# EasyEDApro.net
KiCad netlist of a schematic drawn in EasyEDA Pro
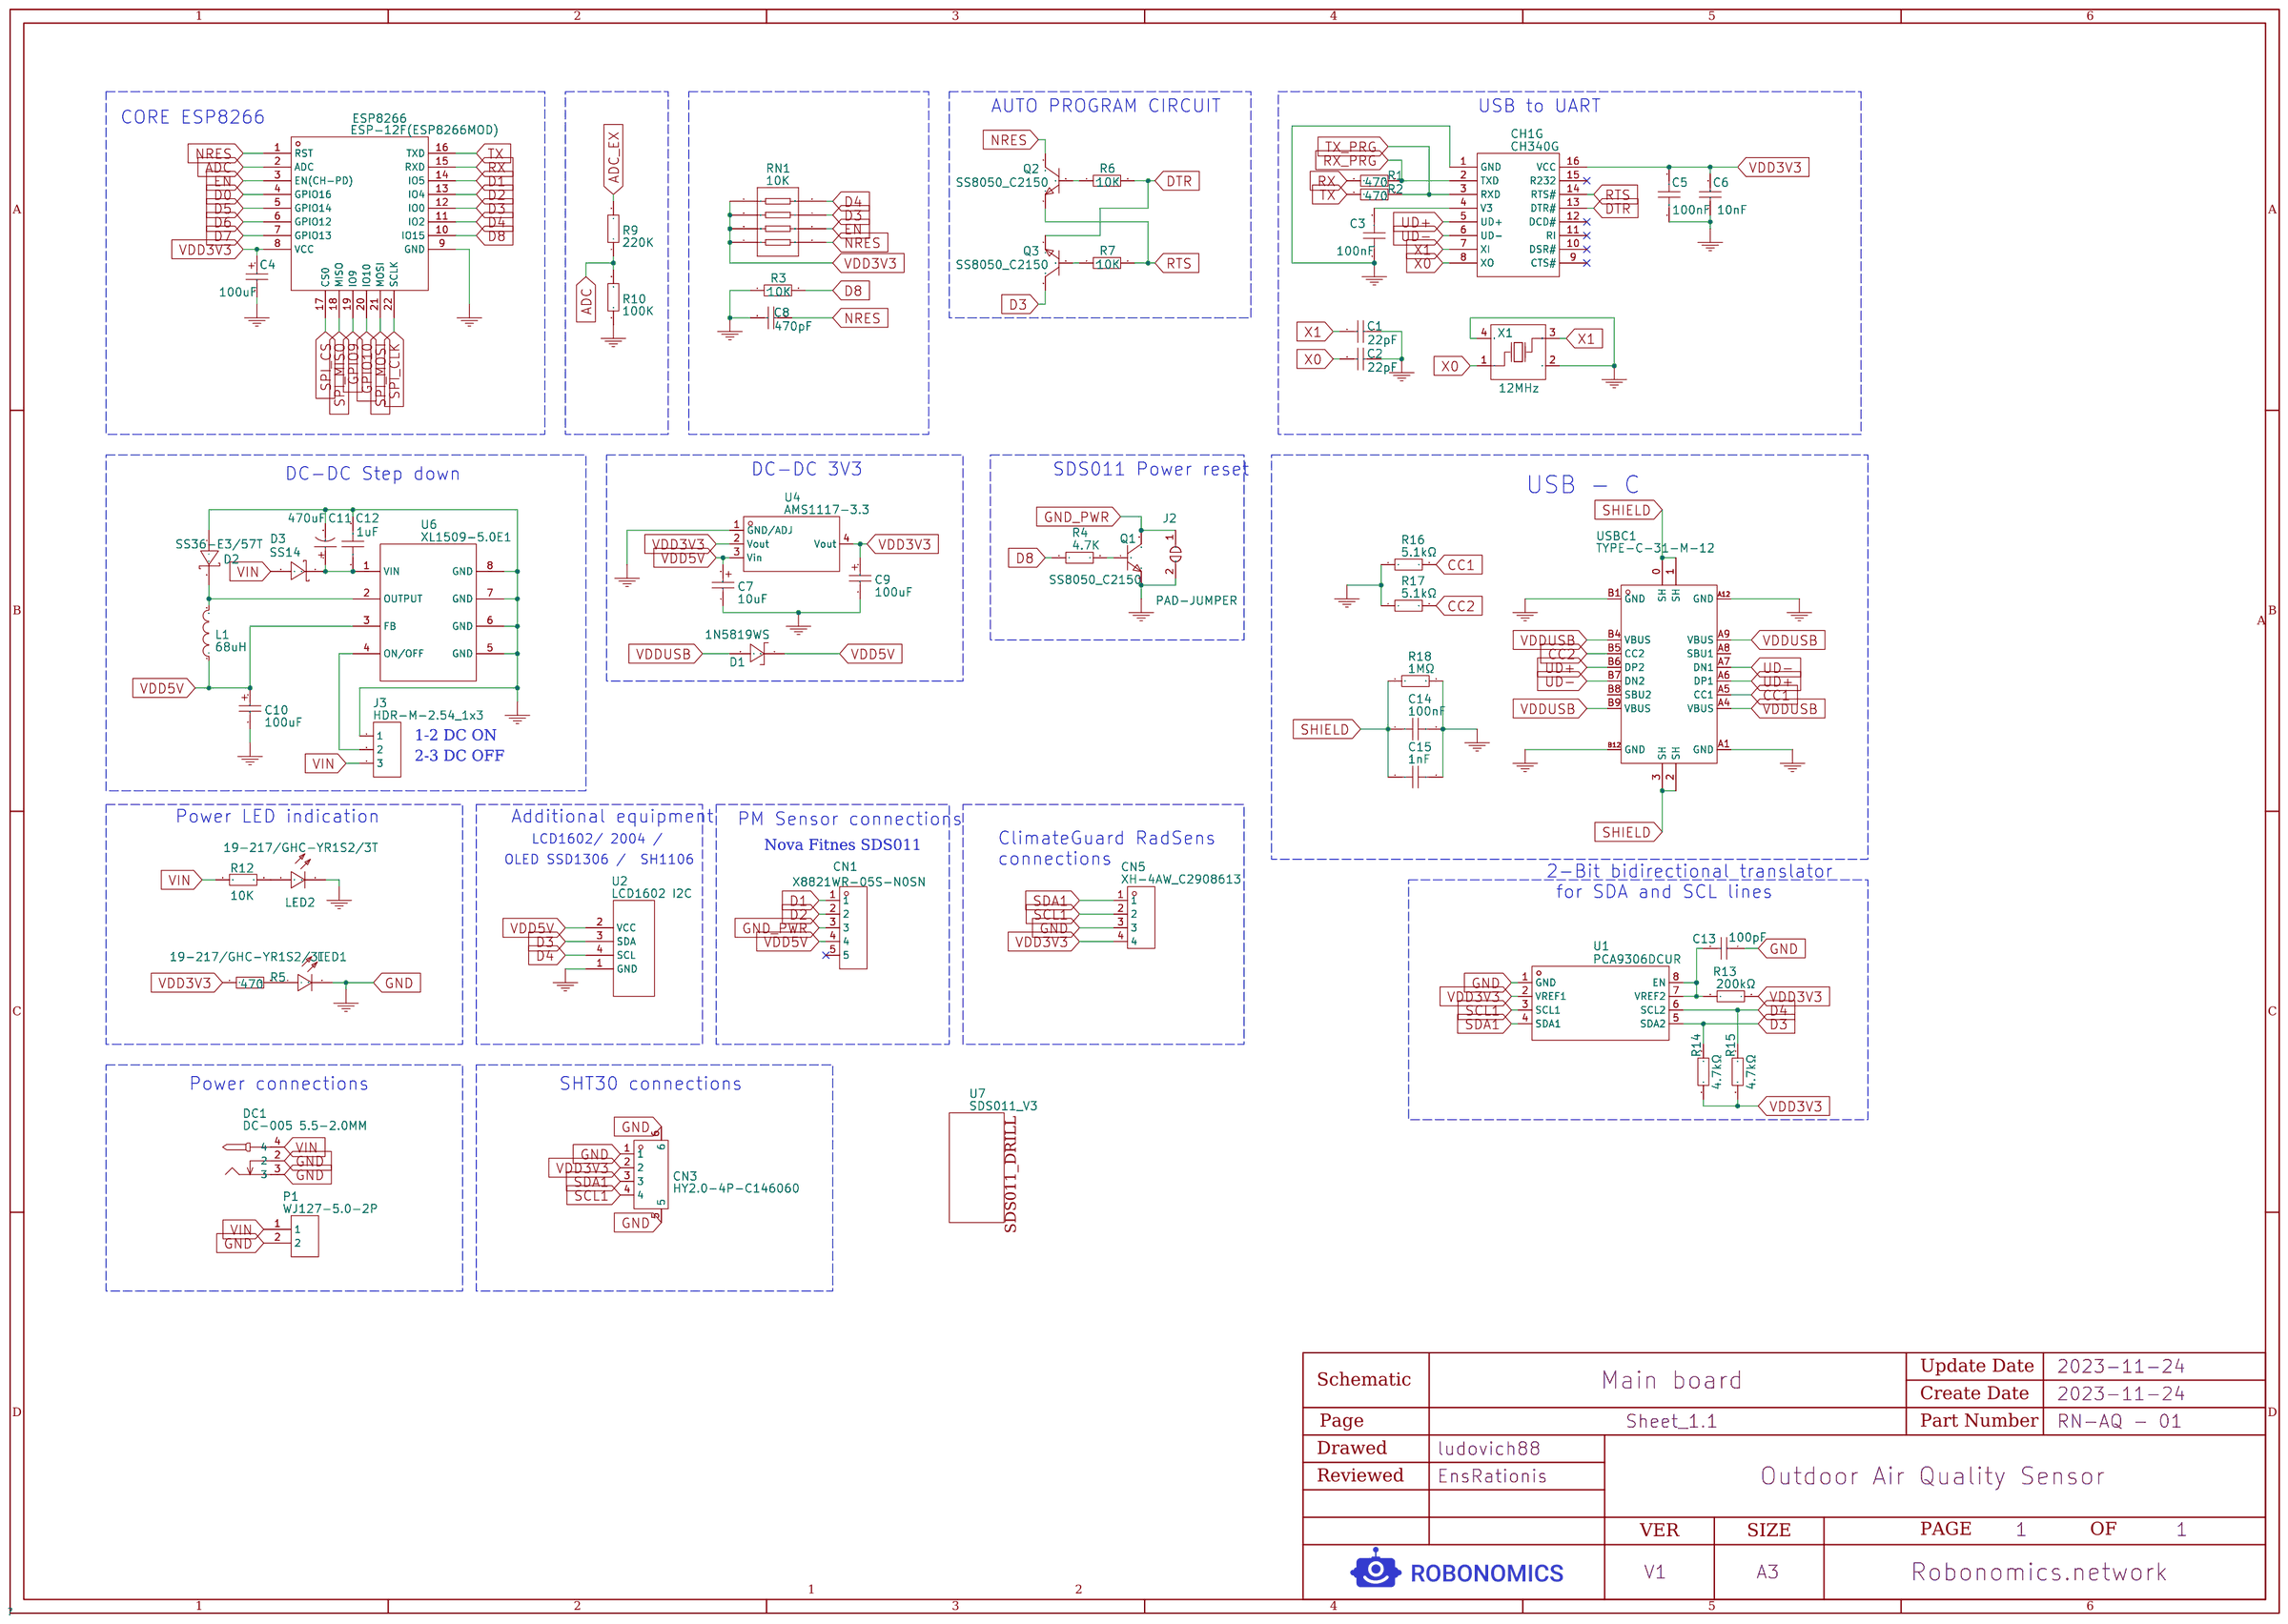
[diagram p0: schematic sheet]

(export (version "E")
  (design (tool "Eeschema 10.0.6"))
  (components
    (comp (ref "C1")
      (value "22pF")
      (footprint "easyedapro:C0603")
      (fields (field (name "Manufacturer Part") "CL10C220JB8NNNC") (field (name "Manufacturer") "SAMSUNG"))
      (libsource (lib "easyedapro") (part "22pF"))
    )
    (comp (ref "C2")
      (value "22pF")
      (footprint "easyedapro:C0603")
      (fields (field (name "Manufacturer Part") "CL10C220JB8NNNC") (field (name "Manufacturer") "SAMSUNG"))
      (libsource (lib "easyedapro") (part "22pF"))
    )
    (comp (ref "C3")
      (value "100nF")
      (footprint "easyedapro:C0603")
      (fields (field (name "Manufacturer Part") "CC0603KRX7R9BB104") (field (name "Manufacturer") "YAGEO"))
      (libsource (lib "easyedapro") (part "100nF"))
    )
    (comp (ref "C4")
      (value "100uF")
      (footprint "easyedapro:CAP-SMD_L3.5-W2.8")
      (fields (field (name "Manufacturer Part") "TAJB107K006RNJ") (field (name "Manufacturer") "AVX"))
      (libsource (lib "easyedapro") (part "100uF"))
    )
    (comp (ref "C5")
      (value "100nF")
      (footprint "easyedapro:C0603")
      (fields (field (name "Manufacturer Part") "CC0603KRX7R9BB104") (field (name "Manufacturer") "YAGEO"))
      (libsource (lib "easyedapro") (part "100nF"))
    )
    (comp (ref "C6")
      (value "10nF")
      (footprint "easyedapro:C0603")
      (fields (field (name "Manufacturer Part") "0603B103K500NT") (field (name "Manufacturer") "FH"))
      (libsource (lib "easyedapro") (part "10nF"))
    )
    (comp (ref "C7")
      (value "10uF")
      (footprint "easyedapro:CAP-SMD_L3.2-W1.6-R-RD")
      (fields (field (name "Manufacturer Part") "CA45-A010M106T") (field (name "Manufacturer") "Xiangyee"))
      (libsource (lib "easyedapro") (part "10uF"))
    )
    (comp (ref "C8")
      (value "470pF")
      (footprint "easyedapro:C0603")
      (fields (field (name "Manufacturer Part") "0603B471K500NT") (field (name "Manufacturer") "FH"))
      (libsource (lib "easyedapro") (part "470pF"))
    )
    (comp (ref "C9")
      (value "100uF")
      (footprint "easyedapro:CAP-SMD_L3.5-W2.8")
      (fields (field (name "Manufacturer Part") "TAJB107K006RNJ") (field (name "Manufacturer") "AVX"))
      (libsource (lib "easyedapro") (part "100uF"))
    )
    (comp (ref "C10")
      (value "100uF")
      (footprint "easyedapro:CAP-SMD_L3.5-W2.8")
      (fields (field (name "Manufacturer Part") "TAJB107K006RNJ") (field (name "Manufacturer") "AVX"))
      (libsource (lib "easyedapro") (part "100uF"))
    )
    (comp (ref "C11")
      (value "470uF")
      (footprint "easyedapro:CAP-SMD_BD10.0-L10.3-W10.3-FD")
      (fields (field (name "Manufacturer Part") "RVT1V471M1010") (field (name "Manufacturer") "HONOR"))
      (libsource (lib "easyedapro") (part "470uF"))
    )
    (comp (ref "C12")
      (value "1uF")
      (footprint "easyedapro:C1206")
      (fields (field (name "Manufacturer Part") "CL31B105KBHNNNE") (field (name "Manufacturer") "SAMSUNG"))
      (libsource (lib "easyedapro") (part "1uF"))
    )
    (comp (ref "C13")
      (value "100pF")
      (footprint "easyedapro:C0603")
      (fields (field (name "Manufacturer Part") "CL10C101JB8NNNC") (field (name "Manufacturer") "SAMSUNG"))
      (libsource (lib "easyedapro") (part "100pF"))
    )
    (comp (ref "C14")
      (value "100nF")
      (footprint "easyedapro:C0603")
      (fields (field (name "Manufacturer Part") "CC0603KRX7R9BB104") (field (name "Manufacturer") "YAGEO"))
      (libsource (lib "easyedapro") (part "100nF"))
    )
    (comp (ref "C15")
      (value "1nF")
      (footprint "easyedapro:C0603")
      (fields
        (field (name "Manufacturer Part") "GRM1885C1H102FA01D")
        (field (name "Manufacturer") "muRata(村田)")
      )
      (libsource (lib "easyedapro") (part "1nF"))
    )
    (comp (ref "CH1G")
      (value "CH340G")
      (footprint "easyedapro:SOIC-16_150MIL")
      (fields (field (name "Manufacturer") "WCH"))
      (libsource (lib "easyedapro") (part "CH340G"))
    )
    (comp (ref "CN1")
      (value "X8821WR-05S-N0SN")
      (footprint "easyedapro:CONN-TH_5P-P2.50_X8821WR-05S-N0SN")
      (fields (field (name "Manufacturer") "XKBConnectivity(中国星坤)"))
      (libsource (lib "easyedapro") (part "X8821WR-05S-N0SN"))
    )
    (comp (ref "CN3")
      (value "HY2.0-4P-C146060")
      (footprint "easyedapro:CONN-SMD_HY2.0-4P")
      (fields (field (name "Manufacturer Part") "HY-4P卧贴") (field (name "Manufacturer") "BOOMELE(博穆精密)"))
      (libsource (lib "easyedapro") (part "HY2.0-4P-C146060"))
    )
    (comp (ref "CN5")
      (value "XH-4AW_C2908613")
      (footprint "easyedapro:CONN-TH_XH-4AW")
      (fields (field (name "Manufacturer Part") "XH-4AW") (field (name "Manufacturer") "HCTL(华灿天禄)"))
      (libsource (lib "easyedapro") (part "XH-4AW_C2908613"))
    )
    (comp (ref "D1")
      (value "1N5819WS")
      (footprint "easyedapro:SOD-323_L1.8-W1.3-LS2.5-RD")
      (fields (field (name "Manufacturer") "GuangdongHottech"))
      (libsource (lib "easyedapro") (part "1N5819WS"))
    )
    (comp (ref "D2")
      (value "SS36-E3/57T")
      (footprint "easyedapro:SMC_L7.1-W6.2-LS8.1-R-RD")
      (fields (field (name "Manufacturer") "VISHAY"))
      (libsource (lib "easyedapro") (part "SS36-E3/57T"))
    )
    (comp (ref "D3")
      (value "SS14")
      (footprint "easyedapro:SMA_L4.4-W2.8-LS5.4-RD")
      (fields (field (name "Manufacturer") "MDD"))
      (libsource (lib "easyedapro") (part "SS14"))
    )
    (comp (ref "DC1")
      (value "DC-005 5.5-2.0MM")
      (footprint "easyedapro:DC-IN-TH_DC-5520-1")
      (fields (field (name "Manufacturer Part") "DC-0052.0") (field (name "Manufacturer") "BOOMELE(博穆精密)"))
      (libsource (lib "easyedapro") (part "DC-005 5.5-2.0MM"))
    )
    (comp (ref "ESP8266")
      (value "ESP-12F(ESP8266MOD)")
      (footprint "easyedapro:WIFIM-SMD_ESP-12F-ESP8266MOD")
      (fields (field (name "Manufacturer") "Ai-Thinker"))
      (libsource (lib "easyedapro") (part "ESP-12F(ESP8266MOD)"))
    )
    (comp (ref "J2")
      (value "PAD-JUMPER")
      (footprint "easyedapro:PAD-JUMPER-2_1")
      (libsource (lib "easyedapro") (part "PAD-JUMPER"))
    )
    (comp (ref "J3")
      (value "HDR-M-2.54_1x3")
      (footprint "easyedapro:HDR-M-2.54_1X3")
      (libsource (lib "easyedapro") (part "HDR-M-2.54_1x3"))
    )
    (comp (ref "L1")
      (value "68uH")
      (footprint "easyedapro:IND-SMD_L11.5-W10.0_SMMS1040")
      (fields
        (field (name "Manufacturer Part") "SMMS1040-680MT")
        (field (name "Manufacturer") "ShunXiangConnaughtElec")
      )
      (libsource (lib "easyedapro") (part "68uH"))
    )
    (comp (ref "LED1")
      (value "19-217/GHC-YR1S2/3T")
      (footprint "easyedapro:LED0603-R-RD")
      (fields (field (name "Manufacturer") "EVERLIGHT"))
      (libsource (lib "easyedapro") (part "19-217/GHC-YR1S2/3T"))
    )
    (comp (ref "LED2")
      (value "19-217/GHC-YR1S2/3T")
      (footprint "easyedapro:LED0603-R-RD")
      (fields (field (name "Manufacturer") "EVERLIGHT"))
      (libsource (lib "easyedapro") (part "19-217/GHC-YR1S2/3T"))
    )
    (comp (ref "P1")
      (value "WJ127-5.0-2P")
      (footprint "easyedapro:CONN-TH_2P-P5.00_CPC3703CTR")
      (fields (field (name "Manufacturer") "KANGNEX(康奈克斯电气)"))
      (libsource (lib "easyedapro") (part "WJ127-5.0-2P"))
    )
    (comp (ref "Q1")
      (value "SS8050_C2150")
      (footprint "easyedapro:SOT-23-3_L2.9-W1.3-P1.90-LS2.4-BR")
      (fields (field (name "Manufacturer Part") "SS8050") (field (name "Manufacturer") "CJ"))
      (libsource (lib "") (part "SS8050_C2150_1"))
    )
    (comp (ref "Q2")
      (value "SS8050_C2150")
      (footprint "easyedapro:SOT-23-3_L2.9-W1.3-P1.90-LS2.4-BR")
      (fields (field (name "Manufacturer Part") "SS8050") (field (name "Manufacturer") "CJ"))
      (libsource (lib "") (part "SS8050_C2150_2"))
    )
    (comp (ref "Q3")
      (value "SS8050_C2150")
      (footprint "easyedapro:SOT-23-3_L2.9-W1.3-P1.90-LS2.4-BR")
      (fields (field (name "Manufacturer Part") "SS8050") (field (name "Manufacturer") "CJ"))
      (libsource (lib "easyedapro") (part "SS8050_C2150"))
    )
    (comp (ref "R1")
      (value "470")
      (footprint "easyedapro:R0603")
      (fields (field (name "Manufacturer Part") "0603WAF4700T5E") (field (name "Manufacturer") "UniOhm"))
      (libsource (lib "easyedapro") (part "470"))
    )
    (comp (ref "R2")
      (value "470")
      (footprint "easyedapro:R0603")
      (fields (field (name "Manufacturer Part") "0603WAF4700T5E") (field (name "Manufacturer") "UniOhm"))
      (libsource (lib "easyedapro") (part "470"))
    )
    (comp (ref "R3")
      (value "10K")
      (footprint "easyedapro:R0603")
      (fields (field (name "Manufacturer Part") "0603WAF1002T5E") (field (name "Manufacturer") "UniOhm"))
      (libsource (lib "easyedapro") (part "10K"))
    )
    (comp (ref "R4")
      (value "4.7K")
      (footprint "easyedapro:R0603")
      (fields (field (name "Manufacturer Part") "0603WAF4701T5E") (field (name "Manufacturer") "UniOhm"))
      (libsource (lib "easyedapro") (part "4.7K"))
    )
    (comp (ref "R5")
      (value "470")
      (footprint "easyedapro:R0603")
      (fields (field (name "Manufacturer Part") "0603WAF4700T5E") (field (name "Manufacturer") "UniOhm"))
      (libsource (lib "easyedapro") (part "470"))
    )
    (comp (ref "R6")
      (value "10K")
      (footprint "easyedapro:R0603")
      (fields (field (name "Manufacturer Part") "0603WAF1002T5E") (field (name "Manufacturer") "UniOhm"))
      (libsource (lib "easyedapro") (part "10K"))
    )
    (comp (ref "R7")
      (value "10K")
      (footprint "easyedapro:R0603")
      (fields (field (name "Manufacturer Part") "0603WAF1002T5E") (field (name "Manufacturer") "UniOhm"))
      (libsource (lib "easyedapro") (part "10K"))
    )
    (comp (ref "R9")
      (value "220K")
      (footprint "easyedapro:R0603")
      (fields (field (name "Manufacturer Part") "0603WAF2203T5E") (field (name "Manufacturer") "UniOhm"))
      (libsource (lib "easyedapro") (part "220K"))
    )
    (comp (ref "R10")
      (value "100K")
      (footprint "easyedapro:R0603")
      (fields (field (name "Manufacturer Part") "0603WAF1003T5E") (field (name "Manufacturer") "UniOhm"))
      (libsource (lib "easyedapro") (part "100K"))
    )
    (comp (ref "R12")
      (value "10K")
      (footprint "easyedapro:R0603")
      (fields (field (name "Manufacturer Part") "0603WAF1002T5E") (field (name "Manufacturer") "UniOhm"))
      (libsource (lib "easyedapro") (part "10K"))
    )
    (comp (ref "R13")
      (value "200kΩ")
      (footprint "easyedapro:R0603")
      (fields (field (name "Manufacturer Part") "0603WAF2003T5E") (field (name "Manufacturer") "UniOhm"))
      (libsource (lib "easyedapro") (part "200kΩ"))
    )
    (comp (ref "R14")
      (value "4.7kΩ")
      (footprint "easyedapro:R0603")
      (fields (field (name "Manufacturer Part") "0603WAF4701T5E") (field (name "Manufacturer") "UniOhm"))
      (libsource (lib "easyedapro") (part "4.7K"))
    )
    (comp (ref "R15")
      (value "4.7kΩ")
      (footprint "easyedapro:R0603")
      (fields (field (name "Manufacturer Part") "0603WAF4701T5E") (field (name "Manufacturer") "UniOhm"))
      (libsource (lib "easyedapro") (part "4.7K"))
    )
    (comp (ref "R16")
      (value "5.1kΩ")
      (footprint "easyedapro:R0603")
      (fields
        (field (name "Manufacturer Part") "0603WAF5101T5E")
        (field (name "Manufacturer") "UNI-ROYAL(厚声)")
      )
      (libsource (lib "easyedapro") (part "5.1kΩ"))
    )
    (comp (ref "R17")
      (value "5.1kΩ")
      (footprint "easyedapro:R0603")
      (fields
        (field (name "Manufacturer Part") "0603WAF5101T5E")
        (field (name "Manufacturer") "UNI-ROYAL(厚声)")
      )
      (libsource (lib "easyedapro") (part "5.1kΩ"))
    )
    (comp (ref "R18")
      (value "1MΩ")
      (footprint "easyedapro:R0603")
      (fields
        (field (name "Manufacturer Part") "0603WAF1004T5E")
        (field (name "Manufacturer") "UNI-ROYAL(厚声)")
      )
      (libsource (lib "easyedapro") (part "1MΩ"))
    )
    (comp (ref "RN1")
      (value "10K")
      (footprint "easyedapro:RES-ARRAY-SMD_0603-8P-L3.2-W1.6-BL")
      (fields (field (name "Manufacturer Part") "4D03WGJ0103T5E") (field (name "Manufacturer") "UniOhm"))
      (libsource (lib "") (part "10K_1"))
    )
    (comp (ref "U1")
      (value "PCA9306DCUR")
      (footprint "easyedapro:SSOP-8_L2.0-W2.3-P0.50-LS3.1-BR")
      (fields (field (name "Manufacturer") "TI"))
      (libsource (lib "easyedapro") (part "PCA9306DCUR"))
    )
    (comp (ref "U2")
      (value "LCD1602 I2C")
      (footprint "easyedapro:LCD1620 I2C")
      (fields (field (name "Manufacturer Part") "LCD1602I2C"))
      (libsource (lib "easyedapro") (part "LCD1602 I2C"))
    )
    (comp (ref "U4")
      (value "AMS1117-3.3")
      (footprint "easyedapro:SOT-223-3_L6.5-W3.4-P2.30-LS7.0-BR")
      (fields (field (name "Manufacturer") "AMS"))
      (libsource (lib "easyedapro") (part "AMS1117-3.3"))
    )
    (comp (ref "U6")
      (value "XL1509-5.0E1")
      (footprint "easyedapro:SOIC-8_L5.0-W4.0-P1.27-LS6.0-BL")
      (fields (field (name "Manufacturer") "XLSEMI"))
      (libsource (lib "easyedapro") (part "XL1509-5.0E1"))
    )
    (comp (ref "U7")
      (value "SDS011_V3")
      (footprint "easyedapro:SDS011_V3")
      (libsource (lib "easyedapro") (part "SDS011_V3"))
    )
    (comp (ref "USBC1")
      (value "TYPE-C-31-M-12")
      (footprint "easyedapro:USB-C_SMD-TYPE-C-31-M-12")
      (fields
        (field (name "Manufacturer Part") "KH-TYPE-C-16P")
        (field (name "Manufacturer") "kinghelm(金航标)")
      )
      (libsource (lib "easyedapro") (part "TYPE-C-31-M-12"))
    )
    (comp (ref "X1")
      (value "12MHz")
      (footprint "easyedapro:OSC-SMD_4P-L3.2-W2.5-BL")
      (fields (field (name "Manufacturer Part") "X322512MSB4SI") (field (name "Manufacturer") "YXC"))
      (libsource (lib "easyedapro") (part "12MHz"))
    )
  )
  (nets
    (net (code "1") (name "ADC") (class "Default")
      (node (ref "ESP8266") (pin "2") (pinfunction "ADC_2") (pintype "input"))
      (node (ref "R10") (pin "2") (pinfunction "2_2") (pintype "input"))
      (node (ref "R9") (pin "1") (pinfunction "1_1") (pintype "input"))
    )
    (net (code "2") (name "ADC_EX") (class "Default")
      (node (ref "R9") (pin "2") (pinfunction "2_2") (pintype "input"))
    )
    (net (code "3") (name "CC1") (class "Default")
      (node (ref "R16") (pin "2") (pinfunction "2_2") (pintype "input"))
      (node (ref "USBC1") (pin "A5") (pinfunction "CC1_A5") (pintype "input"))
    )
    (net (code "4") (name "CC2") (class "Default")
      (node (ref "R17") (pin "2") (pinfunction "2_2") (pintype "input"))
      (node (ref "USBC1") (pin "B5") (pinfunction "CC2_B5") (pintype "input"))
    )
    (net (code "5") (name "D0") (class "Default")
      (node (ref "ESP8266") (pin "4") (pinfunction "GPIO16_4") (pintype "input"))
    )
    (net (code "6") (name "D1") (class "Default")
      (node (ref "CN1") (pin "1") (pinfunction "1_1") (pintype "input"))
      (node (ref "ESP8266") (pin "14") (pinfunction "IO5_14") (pintype "input"))
    )
    (net (code "7") (name "D2") (class "Default")
      (node (ref "CN1") (pin "2") (pinfunction "2_2") (pintype "input"))
      (node (ref "ESP8266") (pin "13") (pinfunction "IO4_13") (pintype "input"))
    )
    (net (code "8") (name "D3") (class "Default")
      (node (ref "ESP8266") (pin "12") (pinfunction "IO0_12") (pintype "input"))
      (node (ref "Q3") (pin "3") (pinfunction "C_3") (pintype "input"))
      (node (ref "R14") (pin "1") (pinfunction "1_1") (pintype "input"))
      (node (ref "RN1") (pin "7") (pinfunction "7_7") (pintype "input"))
      (node (ref "U1") (pin "5") (pinfunction "SDA2_5") (pintype "input"))
      (node (ref "U2") (pin "3") (pinfunction "SDA_3") (pintype "input"))
    )
    (net (code "9") (name "D4") (class "Default")
      (node (ref "ESP8266") (pin "11") (pinfunction "IO2_11") (pintype "input"))
      (node (ref "R15") (pin "1") (pinfunction "1_1") (pintype "input"))
      (node (ref "RN1") (pin "8") (pinfunction "8_8") (pintype "input"))
      (node (ref "U1") (pin "6") (pinfunction "SCL2_6") (pintype "input"))
      (node (ref "U2") (pin "4") (pinfunction "SCL_4") (pintype "input"))
    )
    (net (code "10") (name "D5") (class "Default")
      (node (ref "ESP8266") (pin "5") (pinfunction "GPIO14_5") (pintype "input"))
    )
    (net (code "11") (name "D6") (class "Default")
      (node (ref "ESP8266") (pin "6") (pinfunction "GPIO12_6") (pintype "input"))
    )
    (net (code "12") (name "D7") (class "Default")
      (node (ref "ESP8266") (pin "7") (pinfunction "GPIO13_7") (pintype "input"))
    )
    (net (code "13") (name "D8") (class "Default")
      (node (ref "ESP8266") (pin "10") (pinfunction "IO15_10") (pintype "input"))
      (node (ref "R3") (pin "2") (pinfunction "2_2") (pintype "input"))
      (node (ref "R4") (pin "1") (pinfunction "1_1") (pintype "input"))
    )
    (net (code "14") (name "DTR") (class "Default")
      (node (ref "CH1G") (pin "13") (pinfunction "DTR#_13") (pintype "input"))
      (node (ref "Q3") (pin "2") (pinfunction "E_2") (pintype "input"))
      (node (ref "R6") (pin "2") (pinfunction "2_2") (pintype "input"))
    )
    (net (code "15") (name "EN") (class "Default")
      (node (ref "ESP8266") (pin "3") (pinfunction "EN(CH-PD)_3") (pintype "input"))
      (node (ref "RN1") (pin "6") (pinfunction "6_6") (pintype "input"))
    )
    (net (code "16") (name "GND") (class "Default")
      (node (ref "C1") (pin "1") (pinfunction "1_1") (pintype "input"))
      (node (ref "C10") (pin "2") (pinfunction "2_2") (pintype "input"))
      (node (ref "C11") (pin "2") (pinfunction "2_2") (pintype "input"))
      (node (ref "C12") (pin "2") (pinfunction "2_2") (pintype "input"))
      (node (ref "C13") (pin "1") (pinfunction "1_1") (pintype "input"))
      (node (ref "C14") (pin "2") (pinfunction "2_2") (pintype "input"))
      (node (ref "C15") (pin "2") (pinfunction "2_2") (pintype "input"))
      (node (ref "C2") (pin "1") (pinfunction "1_1") (pintype "input"))
      (node (ref "C3") (pin "1") (pinfunction "1_1") (pintype "input"))
      (node (ref "C4") (pin "2") (pinfunction "2_2") (pintype "input"))
      (node (ref "C5") (pin "1") (pinfunction "1_1") (pintype "input"))
      (node (ref "C6") (pin "1") (pinfunction "1_1") (pintype "input"))
      (node (ref "C7") (pin "1") (pinfunction "1_1") (pintype "input"))
      (node (ref "C8") (pin "1") (pinfunction "1_1") (pintype "input"))
      (node (ref "C9") (pin "2") (pinfunction "2_2") (pintype "input"))
      (node (ref "CH1G") (pin "1") (pinfunction "GND_1") (pintype "input"))
      (node (ref "CN3") (pin "1") (pinfunction "1_1") (pintype "input"))
      (node (ref "CN3") (pin "5") (pinfunction "5_5") (pintype "input"))
      (node (ref "CN3") (pin "6") (pinfunction "6_6") (pintype "input"))
      (node (ref "CN5") (pin "3") (pinfunction "3_3") (pintype "input"))
      (node (ref "D2") (pin "1") (pinfunction "A_1") (pintype "input"))
      (node (ref "DC1") (pin "2") (pinfunction "2_2") (pintype "input"))
      (node (ref "DC1") (pin "3") (pinfunction "3_3") (pintype "input"))
      (node (ref "ESP8266") (pin "9") (pinfunction "GND_9") (pintype "input"))
      (node (ref "J2") (pin "2") (pinfunction "B_2") (pintype "input"))
      (node (ref "J3") (pin "1") (pinfunction "1_1") (pintype "input"))
      (node (ref "LED1") (pin "2") (pinfunction "C_2") (pintype "input"))
      (node (ref "LED2") (pin "2") (pinfunction "C_2") (pintype "input"))
      (node (ref "P1") (pin "2") (pinfunction "2_2") (pintype "input"))
      (node (ref "Q1") (pin "2") (pinfunction "E_2") (pintype "input"))
      (node (ref "R10") (pin "1") (pinfunction "1_1") (pintype "input"))
      (node (ref "R16") (pin "1") (pinfunction "1_1") (pintype "input"))
      (node (ref "R17") (pin "1") (pinfunction "1_1") (pintype "input"))
      (node (ref "R18") (pin "2") (pinfunction "2_2") (pintype "input"))
      (node (ref "R3") (pin "1") (pinfunction "1_1") (pintype "input"))
      (node (ref "U1") (pin "1") (pinfunction "GND_1") (pintype "input"))
      (node (ref "U2") (pin "1") (pinfunction "GND_1") (pintype "input"))
      (node (ref "U4") (pin "1") (pinfunction "GND/ADJ_1") (pintype "input"))
      (node (ref "U6") (pin "5") (pinfunction "GND_5") (pintype "input"))
      (node (ref "U6") (pin "6") (pinfunction "GND_6") (pintype "input"))
      (node (ref "U6") (pin "7") (pinfunction "GND_7") (pintype "input"))
      (node (ref "U6") (pin "8") (pinfunction "GND_8") (pintype "input"))
      (node (ref "USBC1") (pin "A1") (pinfunction "GND_A1") (pintype "input"))
      (node (ref "USBC1") (pin "A12") (pinfunction "GND_A12") (pintype "input"))
      (node (ref "USBC1") (pin "B1") (pinfunction "GND_B1") (pintype "input"))
      (node (ref "USBC1") (pin "B12") (pinfunction "GND_B12") (pintype "input"))
      (node (ref "X1") (pin "2") (pinfunction "GND_2") (pintype "input"))
      (node (ref "X1") (pin "4") (pinfunction "GND_4") (pintype "input"))
    )
    (net (code "17") (name "GND_PWR") (class "Default")
      (node (ref "CN1") (pin "3") (pinfunction "3_3") (pintype "input"))
      (node (ref "J2") (pin "1") (pinfunction "A_1") (pintype "input"))
      (node (ref "Q1") (pin "3") (pinfunction "C_3") (pintype "input"))
    )
    (net (code "18") (name "GPIO9") (class "Default")
      (node (ref "ESP8266") (pin "19") (pinfunction "IO9_19") (pintype "input"))
    )
    (net (code "19") (name "GPIO10") (class "Default")
      (node (ref "ESP8266") (pin "20") (pinfunction "IO10_20") (pintype "input"))
    )
    (net (code "20") (name "NRES") (class "Default")
      (node (ref "C8") (pin "2") (pinfunction "2_2") (pintype "input"))
      (node (ref "ESP8266") (pin "1") (pinfunction "RST_1") (pintype "input"))
      (node (ref "Q2") (pin "3") (pinfunction "C_3") (pintype "input"))
      (node (ref "RN1") (pin "5") (pinfunction "5_5") (pintype "input"))
    )
    (net (code "21") (name "Net-(CH1G-V3)") (class "Default")
      (node (ref "C3") (pin "2") (pinfunction "2_2") (pintype "input"))
      (node (ref "CH1G") (pin "4") (pinfunction "V3_4") (pintype "input"))
    )
    (net (code "22") (name "Net-(D2-K)") (class "Default")
      (node (ref "D2") (pin "2") (pinfunction "K_2") (pintype "input"))
      (node (ref "L1") (pin "2") (pinfunction "2_2") (pintype "input"))
      (node (ref "U6") (pin "2") (pinfunction "OUTPUT_2") (pintype "input"))
    )
    (net (code "23") (name "Net-(D3-K)") (class "Default")
      (node (ref "C11") (pin "1") (pinfunction "1_1") (pintype "input"))
      (node (ref "C12") (pin "1") (pinfunction "1_1") (pintype "input"))
      (node (ref "D3") (pin "1") (pinfunction "K_1") (pintype "input"))
      (node (ref "U6") (pin "1") (pinfunction "VIN_1") (pintype "input"))
    )
    (net (code "24") (name "Net-(LED1-A)") (class "Default")
      (node (ref "LED1") (pin "1") (pinfunction "A_1") (pintype "input"))
      (node (ref "R5") (pin "2") (pinfunction "2_2") (pintype "input"))
    )
    (net (code "25") (name "Net-(LED2-A)") (class "Default")
      (node (ref "LED2") (pin "1") (pinfunction "A_1") (pintype "input"))
      (node (ref "R12") (pin "2") (pinfunction "2_2") (pintype "input"))
    )
    (net (code "26") (name "Net-(Q1-B)") (class "Default")
      (node (ref "Q1") (pin "1") (pinfunction "B_1") (pintype "input"))
      (node (ref "R4") (pin "2") (pinfunction "2_2") (pintype "input"))
    )
    (net (code "27") (name "Net-(Q2-B)") (class "Default")
      (node (ref "Q2") (pin "1") (pinfunction "B_1") (pintype "input"))
      (node (ref "R6") (pin "1") (pinfunction "1_1") (pintype "input"))
    )
    (net (code "28") (name "Net-(Q3-B)") (class "Default")
      (node (ref "Q3") (pin "1") (pinfunction "B_1") (pintype "input"))
      (node (ref "R7") (pin "1") (pinfunction "1_1") (pintype "input"))
    )
    (net (code "29") (name "Net-(U1-EN)") (class "Default")
      (node (ref "C13") (pin "2") (pinfunction "2_2") (pintype "input"))
      (node (ref "R13") (pin "1") (pinfunction "1_1") (pintype "input"))
      (node (ref "U1") (pin "7") (pinfunction "VREF2_7") (pintype "input"))
      (node (ref "U1") (pin "8") (pinfunction "EN_8") (pintype "input"))
    )
    (net (code "30") (name "Net-(U6-ON{slash}OFF)") (class "Default")
      (node (ref "J3") (pin "2") (pinfunction "2_2") (pintype "input"))
      (node (ref "U6") (pin "4") (pinfunction "ON/OFF_4") (pintype "input"))
    )
    (net (code "31") (name "RTS") (class "Default")
      (node (ref "CH1G") (pin "14") (pinfunction "RTS#_14") (pintype "input"))
      (node (ref "Q2") (pin "2") (pinfunction "E_2") (pintype "input"))
      (node (ref "R7") (pin "2") (pinfunction "2_2") (pintype "input"))
    )
    (net (code "32") (name "RX") (class "Default")
      (node (ref "ESP8266") (pin "15") (pinfunction "RXD_15") (pintype "input"))
      (node (ref "R1") (pin "1") (pinfunction "1_1") (pintype "input"))
    )
    (net (code "33") (name "RX_PRG") (class "Default")
      (node (ref "CH1G") (pin "2") (pinfunction "TXD_2") (pintype "input"))
      (node (ref "R1") (pin "2") (pinfunction "2_2") (pintype "input"))
    )
    (net (code "34") (name "SCL1") (class "Default")
      (node (ref "CN3") (pin "4") (pinfunction "4_4") (pintype "input"))
      (node (ref "CN5") (pin "2") (pinfunction "2_2") (pintype "input"))
      (node (ref "U1") (pin "3") (pinfunction "SCL1_3") (pintype "input"))
    )
    (net (code "35") (name "SDA1") (class "Default")
      (node (ref "CN3") (pin "3") (pinfunction "3_3") (pintype "input"))
      (node (ref "CN5") (pin "1") (pinfunction "1_1") (pintype "input"))
      (node (ref "U1") (pin "4") (pinfunction "SDA1_4") (pintype "input"))
    )
    (net (code "36") (name "SHIELD") (class "Default")
      (node (ref "C14") (pin "1") (pinfunction "1_1") (pintype "input"))
      (node (ref "C15") (pin "1") (pinfunction "1_1") (pintype "input"))
      (node (ref "R18") (pin "1") (pinfunction "1_1") (pintype "input"))
      (node (ref "USBC1") (pin "0") (pinfunction "SH_0") (pintype "input"))
      (node (ref "USBC1") (pin "1") (pinfunction "SH_1") (pintype "input"))
      (node (ref "USBC1") (pin "2") (pinfunction "SH_2") (pintype "input"))
      (node (ref "USBC1") (pin "3") (pinfunction "SH_3") (pintype "input"))
    )
    (net (code "37") (name "SPI_CLK") (class "Default")
      (node (ref "ESP8266") (pin "22") (pinfunction "SCLK_22") (pintype "input"))
    )
    (net (code "38") (name "SPI_CS") (class "Default")
      (node (ref "ESP8266") (pin "17") (pinfunction "CS0_17") (pintype "input"))
    )
    (net (code "39") (name "SPI_MISO") (class "Default")
      (node (ref "ESP8266") (pin "18") (pinfunction "MISO_18") (pintype "input"))
    )
    (net (code "40") (name "SPI_MOSI") (class "Default")
      (node (ref "ESP8266") (pin "21") (pinfunction "MOSI_21") (pintype "input"))
    )
    (net (code "41") (name "TX") (class "Default")
      (node (ref "ESP8266") (pin "16") (pinfunction "TXD_16") (pintype "input"))
      (node (ref "R2") (pin "1") (pinfunction "1_1") (pintype "input"))
    )
    (net (code "42") (name "TX_PRG") (class "Default")
      (node (ref "CH1G") (pin "3") (pinfunction "RXD_3") (pintype "input"))
      (node (ref "R2") (pin "2") (pinfunction "2_2") (pintype "input"))
    )
    (net (code "43") (name "UD+") (class "Default")
      (node (ref "CH1G") (pin "5") (pinfunction "UD+_5") (pintype "input"))
      (node (ref "USBC1") (pin "A6") (pinfunction "DP1_A6") (pintype "input"))
      (node (ref "USBC1") (pin "B6") (pinfunction "DP2_B6") (pintype "input"))
    )
    (net (code "44") (name "UD-") (class "Default")
      (node (ref "CH1G") (pin "6") (pinfunction "UD-_6") (pintype "input"))
      (node (ref "USBC1") (pin "A7") (pinfunction "DN1_A7") (pintype "input"))
      (node (ref "USBC1") (pin "B7") (pinfunction "DN2_B7") (pintype "input"))
    )
    (net (code "45") (name "VDD3V3") (class "Default")
      (node (ref "C4") (pin "1") (pinfunction "1_1") (pintype "input"))
      (node (ref "C5") (pin "2") (pinfunction "2_2") (pintype "input"))
      (node (ref "C6") (pin "2") (pinfunction "2_2") (pintype "input"))
      (node (ref "C9") (pin "1") (pinfunction "1_1") (pintype "input"))
      (node (ref "CH1G") (pin "16") (pinfunction "VCC_16") (pintype "input"))
      (node (ref "CN3") (pin "2") (pinfunction "2_2") (pintype "input"))
      (node (ref "CN5") (pin "4") (pinfunction "4_4") (pintype "input"))
      (node (ref "ESP8266") (pin "8") (pinfunction "VCC_8") (pintype "input"))
      (node (ref "R13") (pin "2") (pinfunction "2_2") (pintype "input"))
      (node (ref "R14") (pin "2") (pinfunction "2_2") (pintype "input"))
      (node (ref "R15") (pin "2") (pinfunction "2_2") (pintype "input"))
      (node (ref "R5") (pin "1") (pinfunction "1_1") (pintype "input"))
      (node (ref "RN1") (pin "1") (pinfunction "1_1") (pintype "input"))
      (node (ref "RN1") (pin "2") (pinfunction "2_2") (pintype "input"))
      (node (ref "RN1") (pin "3") (pinfunction "3_3") (pintype "input"))
      (node (ref "RN1") (pin "4") (pinfunction "4_4") (pintype "input"))
      (node (ref "U1") (pin "2") (pinfunction "VREF1_2") (pintype "input"))
      (node (ref "U4") (pin "2") (pinfunction "Vout_2") (pintype "input"))
      (node (ref "U4") (pin "4") (pinfunction "Vout_4") (pintype "input"))
    )
    (net (code "46") (name "VDD5V") (class "Default")
      (node (ref "C10") (pin "1") (pinfunction "1_1") (pintype "input"))
      (node (ref "C7") (pin "2") (pinfunction "2_2") (pintype "input"))
      (node (ref "CN1") (pin "4") (pinfunction "4_4") (pintype "input"))
      (node (ref "D1") (pin "1") (pinfunction "C_1") (pintype "input"))
      (node (ref "L1") (pin "1") (pinfunction "1_1") (pintype "input"))
      (node (ref "U2") (pin "2") (pinfunction "VCC_2") (pintype "input"))
      (node (ref "U4") (pin "3") (pinfunction "Vin_3") (pintype "input"))
      (node (ref "U6") (pin "3") (pinfunction "FB_3") (pintype "input"))
    )
    (net (code "47") (name "VDDUSB") (class "Default")
      (node (ref "D1") (pin "2") (pinfunction "A_2") (pintype "input"))
      (node (ref "USBC1") (pin "A4") (pinfunction "VBUS_A4") (pintype "input"))
      (node (ref "USBC1") (pin "A9") (pinfunction "VBUS_A9") (pintype "input"))
      (node (ref "USBC1") (pin "B4") (pinfunction "VBUS_B4") (pintype "input"))
      (node (ref "USBC1") (pin "B9") (pinfunction "VBUS_B9") (pintype "input"))
    )
    (net (code "48") (name "VIN") (class "Default")
      (node (ref "D3") (pin "2") (pinfunction "A_2") (pintype "input"))
      (node (ref "DC1") (pin "4") (pinfunction "4_4") (pintype "input"))
      (node (ref "J3") (pin "3") (pinfunction "3_3") (pintype "input"))
      (node (ref "P1") (pin "1") (pinfunction "1_1") (pintype "input"))
      (node (ref "R12") (pin "1") (pinfunction "1_1") (pintype "input"))
    )
    (net (code "49") (name "X0") (class "Default")
      (node (ref "C2") (pin "2") (pinfunction "2_2") (pintype "input"))
      (node (ref "CH1G") (pin "8") (pinfunction "XO_8") (pintype "input"))
      (node (ref "X1") (pin "1") (pinfunction "OSC1_1") (pintype "input"))
    )
    (net (code "50") (name "X1") (class "Default")
      (node (ref "C1") (pin "2") (pinfunction "2_2") (pintype "input"))
      (node (ref "CH1G") (pin "7") (pinfunction "XI_7") (pintype "input"))
      (node (ref "X1") (pin "3") (pinfunction "OSC2_3") (pintype "input"))
    )
    (net (code "51") (name "unconnected-(CH1G-CTS#-Pad9)") (class "Default")
      (node (ref "CH1G") (pin "9") (pinfunction "CTS#_9") (pintype "input+no_connect"))
    )
    (net (code "52") (name "unconnected-(CH1G-DCD#-Pad12)") (class "Default")
      (node (ref "CH1G") (pin "12") (pinfunction "DCD#_12") (pintype "input+no_connect"))
    )
    (net (code "53") (name "unconnected-(CH1G-DSR#-Pad10)") (class "Default")
      (node (ref "CH1G") (pin "10") (pinfunction "DSR#_10") (pintype "input+no_connect"))
    )
    (net (code "54") (name "unconnected-(CH1G-R232-Pad15)") (class "Default")
      (node (ref "CH1G") (pin "15") (pinfunction "R232_15") (pintype "input+no_connect"))
    )
    (net (code "55") (name "unconnected-(CH1G-RI-Pad11)") (class "Default")
      (node (ref "CH1G") (pin "11") (pinfunction "RI_11") (pintype "input+no_connect"))
    )
    (net (code "56") (name "unconnected-(CN1-Pad5)") (class "Default")
      (node (ref "CN1") (pin "5") (pinfunction "5_5") (pintype "input+no_connect"))
    )
    (net (code "57") (name "unconnected-(USBC1-SBU1-PadA8)") (class "Default")
      (node (ref "USBC1") (pin "A8") (pinfunction "SBU1_A8") (pintype "input"))
    )
    (net (code "58") (name "unconnected-(USBC1-SBU2-PadB8)") (class "Default")
      (node (ref "USBC1") (pin "B8") (pinfunction "SBU2_B8") (pintype "input"))
    )
  )
)
